# Clock_Circuit.net
KiCad netlist of a schematic drawn in EAGLE
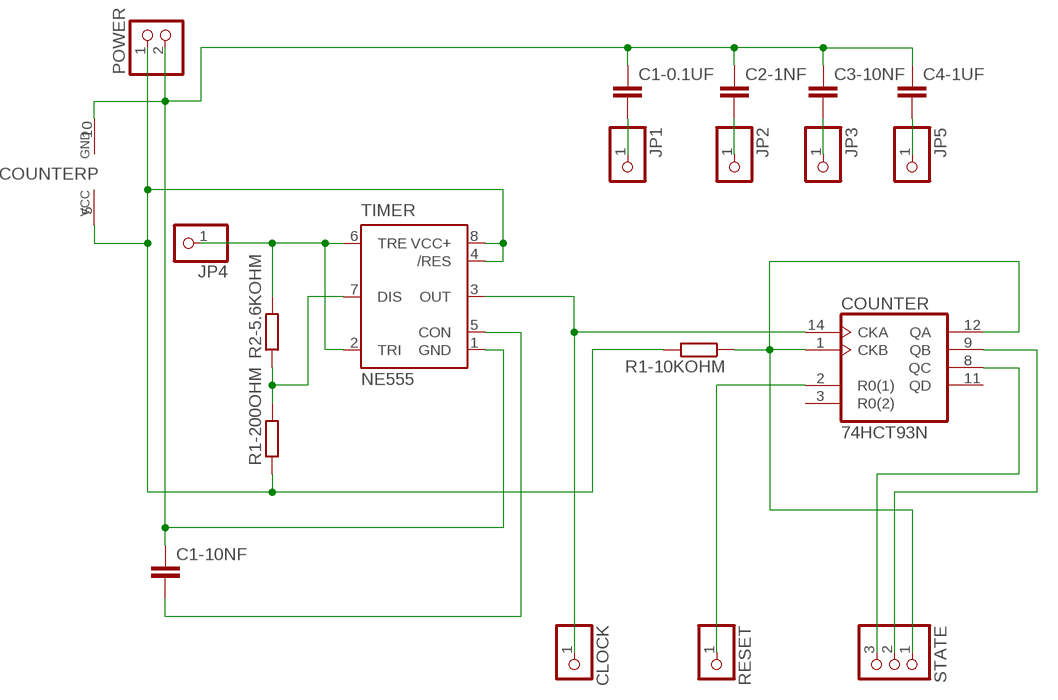
[diagram p0: schematic, sheet 1]

(export (version "E")
  (design (tool "Eeschema 10.0.6"))
  (components
    (comp (ref "C1-0.1UF")
      (value "C-EU050-025X075")
      (footprint "eagle-import:C050-025X075")
      (libsource (lib "eagle-import") (part "C-EU050-025X075"))
    )
    (comp (ref "C1-10NF")
      (value "C-EU050-025X075")
      (footprint "eagle-import:C050-025X075")
      (libsource (lib "eagle-import") (part "C-EU050-025X075"))
    )
    (comp (ref "C2-1NF")
      (value "C-EU050-025X075")
      (footprint "eagle-import:C050-025X075")
      (libsource (lib "eagle-import") (part "C-EU050-025X075"))
    )
    (comp (ref "C3-10NF")
      (value "C-EU050-025X075")
      (footprint "eagle-import:C050-025X075")
      (libsource (lib "eagle-import") (part "C-EU050-025X075"))
    )
    (comp (ref "C4-1UF")
      (value "C-EU050-025X075")
      (footprint "eagle-import:C050-025X075")
      (libsource (lib "eagle-import") (part "C-EU050-025X075"))
    )
    (comp (ref "CLOCK")
      (value "PINHD-1X1")
      (footprint "eagle-import:1X01")
      (libsource (lib "eagle-import") (part "PINHD-1X1"))
    )
    (comp (ref "COUNTER")
      (value "74HCT93N")
      (footprint "eagle-import:DIL14")
      (libsource (lib "eagle-import") (part "7493NHCT"))
    )
    (comp (ref "JP1")
      (value "PINHD-1X1")
      (footprint "eagle-import:1X01")
      (libsource (lib "eagle-import") (part "PINHD-1X1"))
    )
    (comp (ref "JP2")
      (value "PINHD-1X1")
      (footprint "eagle-import:1X01")
      (libsource (lib "eagle-import") (part "PINHD-1X1"))
    )
    (comp (ref "JP3")
      (value "PINHD-1X1")
      (footprint "eagle-import:1X01")
      (libsource (lib "eagle-import") (part "PINHD-1X1"))
    )
    (comp (ref "JP4")
      (value "PINHD-1X1")
      (footprint "eagle-import:1X01")
      (libsource (lib "eagle-import") (part "PINHD-1X1"))
    )
    (comp (ref "JP5")
      (value "PINHD-1X1")
      (footprint "eagle-import:1X01")
      (libsource (lib "eagle-import") (part "PINHD-1X1"))
    )
    (comp (ref "POWER")
      (value "PINHD-1X2")
      (footprint "eagle-import:1X02")
      (libsource (lib "eagle-import") (part "PINHD-1X2"))
    )
    (comp (ref "R1-10KOHM")
      (value "R-EU_0207/10")
      (footprint "eagle-import:0207_10")
      (libsource (lib "eagle-import") (part "R-EU_0207/10"))
    )
    (comp (ref "R1-200OHM")
      (value "R-EU_0207/10")
      (footprint "eagle-import:0207_10")
      (libsource (lib "eagle-import") (part "R-EU_0207/10"))
    )
    (comp (ref "R2-5.6KOHM")
      (value "R-EU_0207/10")
      (footprint "eagle-import:0207_10")
      (libsource (lib "eagle-import") (part "R-EU_0207/10"))
    )
    (comp (ref "RESET")
      (value "PINHD-1X1")
      (footprint "eagle-import:1X01")
      (libsource (lib "eagle-import") (part "PINHD-1X1"))
    )
    (comp (ref "STATE")
      (value "PINHD-1X3")
      (footprint "eagle-import:1X03")
      (libsource (lib "eagle-import") (part "PINHD-1X3"))
    )
    (comp (ref "TIMER")
      (value "NE555")
      (footprint "eagle-import:DIL-08")
      (fields (field (name "MF") "Arrow Electronics") (field (name "MPN") "NE555N"))
      (libsource (lib "eagle-import") (part "NE555"))
    )
  )
  (nets
    (net (code "1") (name "Net-(C1-0.1UF-Pad2)") (class "Default")
      (node (ref "C1-0.1UF") (pin "2") (pinfunction "2_2") (pintype "passive"))
      (node (ref "JP1") (pin "1") (pinfunction "1_1") (pintype "passive"))
    )
    (net (code "2") (name "Net-(C2-1NF-Pad2)") (class "Default")
      (node (ref "C2-1NF") (pin "2") (pinfunction "2_2") (pintype "passive"))
      (node (ref "JP2") (pin "1") (pinfunction "1_1") (pintype "passive"))
    )
    (net (code "3") (name "Net-(C3-10NF-Pad2)") (class "Default")
      (node (ref "C3-10NF") (pin "2") (pinfunction "2_2") (pintype "passive"))
      (node (ref "JP3") (pin "1") (pinfunction "1_1") (pintype "passive"))
    )
    (net (code "4") (name "Net-(C4-1UF-Pad2)") (class "Default")
      (node (ref "C4-1UF") (pin "2") (pinfunction "2_2") (pintype "passive"))
      (node (ref "JP5") (pin "1") (pinfunction "1_1") (pintype "passive"))
    )
    (net (code "5") (name "Net-(COUNTERA-CKA)") (class "Default")
      (node (ref "CLOCK") (pin "1") (pinfunction "1_1") (pintype "passive"))
      (node (ref "COUNTER") (pin "14") (pinfunction "CKA_14") (pintype "input"))
      (node (ref "TIMER") (pin "3") (pinfunction "OUT_3") (pintype "output"))
    )
    (net (code "6") (name "Net-(COUNTERA-CKB)") (class "Default")
      (node (ref "COUNTER") (pin "1") (pinfunction "CKB_1") (pintype "input"))
      (node (ref "COUNTER") (pin "12") (pinfunction "QA_12") (pintype "output"))
      (node (ref "R1-10KOHM") (pin "1") (pinfunction "1_1") (pintype "passive"))
      (node (ref "STATE") (pin "1") (pinfunction "1_1") (pintype "passive"))
    )
    (net (code "7") (name "Net-(COUNTERA-QB)") (class "Default")
      (node (ref "COUNTER") (pin "9") (pinfunction "QB_9") (pintype "output"))
      (node (ref "STATE") (pin "2") (pinfunction "2_2") (pintype "passive"))
    )
    (net (code "8") (name "Net-(COUNTERA-QC)") (class "Default")
      (node (ref "COUNTER") (pin "8") (pinfunction "QC_8") (pintype "output"))
      (node (ref "STATE") (pin "3") (pinfunction "3_3") (pintype "passive"))
    )
    (net (code "9") (name "Net-(COUNTERA-R0(1))") (class "Default")
      (node (ref "COUNTER") (pin "2") (pinfunction "R0(1)_2") (pintype "input"))
      (node (ref "RESET") (pin "1") (pinfunction "1_1") (pintype "passive"))
    )
    (net (code "10") (name "Net-(COUNTERB-GND)") (class "Default")
      (node (ref "C1-0.1UF") (pin "1") (pinfunction "1_1") (pintype "passive"))
      (node (ref "C1-10NF") (pin "1") (pinfunction "1_1") (pintype "passive"))
      (node (ref "C2-1NF") (pin "1") (pinfunction "1_1") (pintype "passive"))
      (node (ref "C3-10NF") (pin "1") (pinfunction "1_1") (pintype "passive"))
      (node (ref "C4-1UF") (pin "1") (pinfunction "1_1") (pintype "passive"))
      (node (ref "COUNTER") (pin "10") (pinfunction "GND_10") (pintype "power_in"))
      (node (ref "POWER") (pin "2") (pinfunction "2_2") (pintype "passive"))
      (node (ref "TIMER") (pin "1") (pinfunction "GND_1") (pintype "power_in"))
    )
    (net (code "11") (name "Net-(COUNTERB-VCC)") (class "Default")
      (node (ref "COUNTER") (pin "5") (pinfunction "VCC_5") (pintype "power_in"))
      (node (ref "POWER") (pin "1") (pinfunction "1_1") (pintype "passive"))
      (node (ref "R1-10KOHM") (pin "2") (pinfunction "2_2") (pintype "passive"))
      (node (ref "R1-200OHM") (pin "1") (pinfunction "1_1") (pintype "passive"))
      (node (ref "TIMER") (pin "4") (pinfunction "/RES_4") (pintype "input"))
      (node (ref "TIMER") (pin "8") (pinfunction "VCC+_8") (pintype "power_in"))
    )
    (net (code "12") (name "Net-(TIMER-CON)") (class "Default")
      (node (ref "C1-10NF") (pin "2") (pinfunction "2_2") (pintype "passive"))
      (node (ref "TIMER") (pin "5") (pinfunction "CON_5") (pintype "input"))
    )
    (net (code "13") (name "Net-(TIMER-DIS)") (class "Default")
      (node (ref "R1-200OHM") (pin "2") (pinfunction "2_2") (pintype "passive"))
      (node (ref "R2-5.6KOHM") (pin "1") (pinfunction "1_1") (pintype "passive"))
      (node (ref "TIMER") (pin "7") (pinfunction "DIS_7") (pintype "input"))
    )
    (net (code "14") (name "Net-(TIMER-TRE)") (class "Default")
      (node (ref "JP4") (pin "1") (pinfunction "1_1") (pintype "passive"))
      (node (ref "R2-5.6KOHM") (pin "2") (pinfunction "2_2") (pintype "passive"))
      (node (ref "TIMER") (pin "2") (pinfunction "TRI_2") (pintype "input"))
      (node (ref "TIMER") (pin "6") (pinfunction "TRE_6") (pintype "input"))
    )
    (net (code "15") (name "unconnected-(COUNTERA-QD-Pad11)") (class "Default")
      (node (ref "COUNTER") (pin "11") (pinfunction "QD_11") (pintype "output"))
    )
    (net (code "16") (name "unconnected-(COUNTERA-R0(2)-Pad3)") (class "Default")
      (node (ref "COUNTER") (pin "3") (pinfunction "R0(2)_3") (pintype "input"))
    )
  )
)
